# MC34063Inverting.net
KiCad netlist of a schematic drawn in Altium Designer
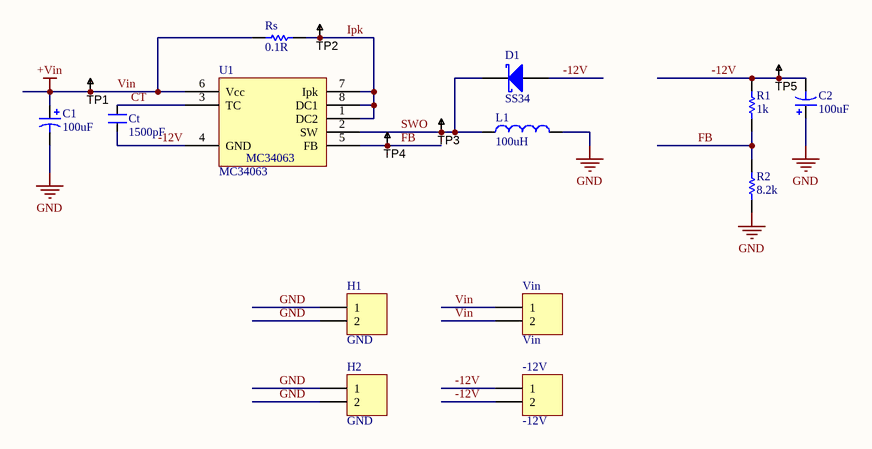
[diagram p0: MC34063Inverting.SchDoc]

(export (version "E")
  (design (tool "Eeschema 10.0.6"))
  (components
    (comp (ref "-12V")
      (value "-12V")
      (footprint "HDR1X2")
      (description "Header, 2-Pin")
      (fields (field (name "PUBLISHER") "Altium Limited"))
      (libsource (lib "Miscellaneous Connectors") (part "Header 2"))
    )
    (comp (ref "C1")
      (value "100uF")
      (footprint "CAP_ELEC_SIZE_H13")
      (fields (field (name "Comment") "Cap"))
      (libsource (lib "Tuan") (part "Cap"))
    )
    (comp (ref "C2")
      (value "100uF")
      (footprint "CAP_ELEC_SIZE_H13")
      (fields (field (name "Comment") "Cap"))
      (libsource (lib "Tuan") (part "Cap"))
    )
    (comp (ref "Ct")
      (value "1500pF")
      (footprint "CAPC2012N_F")
      (fields (field (name "Comment") "CAP NP"))
      (libsource (lib "Tuan") (part "CAP NP"))
    )
    (comp (ref "D1") (value "SS34") (footprint "DO-214AC") (libsource (lib "Tuan") (part "Diode Schottky")))
    (comp (ref "H1")
      (value "GND")
      (footprint "HDR1X2")
      (description "Header, 2-Pin")
      (fields (field (name "PUBLISHER") "Altium Limited"))
      (libsource (lib "Miscellaneous Connectors") (part "Header 2"))
    )
    (comp (ref "H2")
      (value "GND")
      (footprint "HDR1X2")
      (description "Header, 2-Pin")
      (fields (field (name "PUBLISHER") "Altium Limited"))
      (libsource (lib "Miscellaneous Connectors") (part "Header 2"))
    )
    (comp (ref "L1")
      (value "100uH")
      (footprint "Inductor C8x10")
      (fields (field (name "Comment") "Inductor"))
      (libsource (lib "Tuan") (part "Inductor"))
    )
    (comp (ref "R1")
      (value "1k")
      (footprint "RESC2012N_F")
      (fields (field (name "Comment") "Res"))
      (libsource (lib "Tuan") (part "Res"))
    )
    (comp (ref "R2")
      (value "8.2k")
      (footprint "RESC2012N_F")
      (fields (field (name "Comment") "Res"))
      (libsource (lib "Tuan") (part "Res"))
    )
    (comp (ref "Rs")
      (value "0.1R")
      (footprint "RESC6332N")
      (fields (field (name "Comment") "Res"))
      (libsource (lib "Tuan") (part "Res"))
    )
    (comp (ref "TP1")
      (value "TESTPOINT")
      (footprint "TP-R60")
      (description "SMD test pin")
      (libsource (lib "PBL - Test Points") (part "TESTPOINT"))
    )
    (comp (ref "TP2")
      (value "TESTPOINT")
      (footprint "TP-R60")
      (description "SMD test pin")
      (libsource (lib "PBL - Test Points") (part "TESTPOINT"))
    )
    (comp (ref "TP3")
      (value "TESTPOINT")
      (footprint "TP-R60")
      (description "SMD test pin")
      (libsource (lib "PBL - Test Points") (part "TESTPOINT"))
    )
    (comp (ref "TP4")
      (value "TESTPOINT")
      (footprint "TP-R60")
      (description "SMD test pin")
      (libsource (lib "PBL - Test Points") (part "TESTPOINT"))
    )
    (comp (ref "TP5")
      (value "TESTPOINT")
      (footprint "TP-R60")
      (description "SMD test pin")
      (libsource (lib "PBL - Test Points") (part "TESTPOINT"))
    )
    (comp (ref "U1") (value "MC34063") (footprint "SO 8") (libsource (lib "Tuan") (part "MC34063")))
    (comp (ref "Vin")
      (value "Vin")
      (footprint "HDR1X2")
      (description "Header, 2-Pin")
      (fields (field (name "PUBLISHER") "Altium Limited"))
      (libsource (lib "Miscellaneous Connectors") (part "Header 2"))
    )
  )
  (nets
    (net (code "1") (name "+Vin") (class "Default")
      (node (ref "C1") (pin "1") (pinfunction "1_1") (pintype "passive"))
      (node (ref "Rs") (pin "1") (pinfunction "1_1") (pintype "passive"))
      (node (ref "TP1") (pin "1") (pintype "passive"))
      (node (ref "U1") (pin "6") (pinfunction "Vcc_6") (pintype "power_in"))
      (node (ref "Vin") (pin "1") (pinfunction "1_1") (pintype "passive"))
      (node (ref "Vin") (pin "2") (pinfunction "2_2") (pintype "passive"))
    )
    (net (code "2") (name "/-12V") (class "Default")
      (node (ref "-12V") (pin "1") (pinfunction "1_1") (pintype "passive"))
      (node (ref "-12V") (pin "2") (pinfunction "2_2") (pintype "passive"))
      (node (ref "C2") (pin "2") (pinfunction "2_2") (pintype "passive"))
      (node (ref "Ct") (pin "1") (pinfunction "1_1") (pintype "passive"))
      (node (ref "D1") (pin "1") (pinfunction "A_1") (pintype "passive"))
      (node (ref "R1") (pin "2") (pinfunction "2_2") (pintype "passive"))
      (node (ref "TP5") (pin "1") (pintype "passive"))
      (node (ref "U1") (pin "4") (pinfunction "GND_4") (pintype "power_in"))
    )
    (net (code "3") (name "/CT") (class "Default")
      (node (ref "Ct") (pin "2") (pinfunction "2_2") (pintype "passive"))
      (node (ref "U1") (pin "3") (pinfunction "TC_3") (pintype "power_in"))
    )
    (net (code "4") (name "/FB") (class "Default")
      (node (ref "R1") (pin "1") (pinfunction "1_1") (pintype "passive"))
      (node (ref "R2") (pin "2") (pinfunction "2_2") (pintype "passive"))
      (node (ref "TP4") (pin "1") (pintype "passive"))
      (node (ref "U1") (pin "5") (pinfunction "FB_5") (pintype "power_in"))
    )
    (net (code "5") (name "/Ipk") (class "Default")
      (node (ref "Rs") (pin "2") (pinfunction "2_2") (pintype "passive"))
      (node (ref "TP2") (pin "1") (pintype "passive"))
      (node (ref "U1") (pin "1") (pinfunction "DC2_1") (pintype "power_in"))
      (node (ref "U1") (pin "7") (pinfunction "Ipk_7") (pintype "power_in"))
      (node (ref "U1") (pin "8") (pinfunction "DC1_8") (pintype "power_in"))
    )
    (net (code "6") (name "/SWO") (class "Default")
      (node (ref "D1") (pin "2") (pinfunction "K_2") (pintype "passive"))
      (node (ref "L1") (pin "1") (pinfunction "1_1") (pintype "passive"))
      (node (ref "TP3") (pin "1") (pintype "passive"))
      (node (ref "U1") (pin "2") (pinfunction "SW_2") (pintype "power_in"))
    )
    (net (code "7") (name "GND") (class "Default")
      (node (ref "C1") (pin "2") (pinfunction "2_2") (pintype "passive"))
      (node (ref "C2") (pin "1") (pinfunction "1_1") (pintype "passive"))
      (node (ref "H1") (pin "1") (pinfunction "1_1") (pintype "passive"))
      (node (ref "H1") (pin "2") (pinfunction "2_2") (pintype "passive"))
      (node (ref "H2") (pin "1") (pinfunction "1_1") (pintype "passive"))
      (node (ref "H2") (pin "2") (pinfunction "2_2") (pintype "passive"))
      (node (ref "L1") (pin "2") (pinfunction "2_2") (pintype "passive"))
      (node (ref "R2") (pin "1") (pinfunction "1_1") (pintype "passive"))
    )
  )
)
